# tsop_pcb.net
KiCad netlist of a schematic drawn in EAGLE
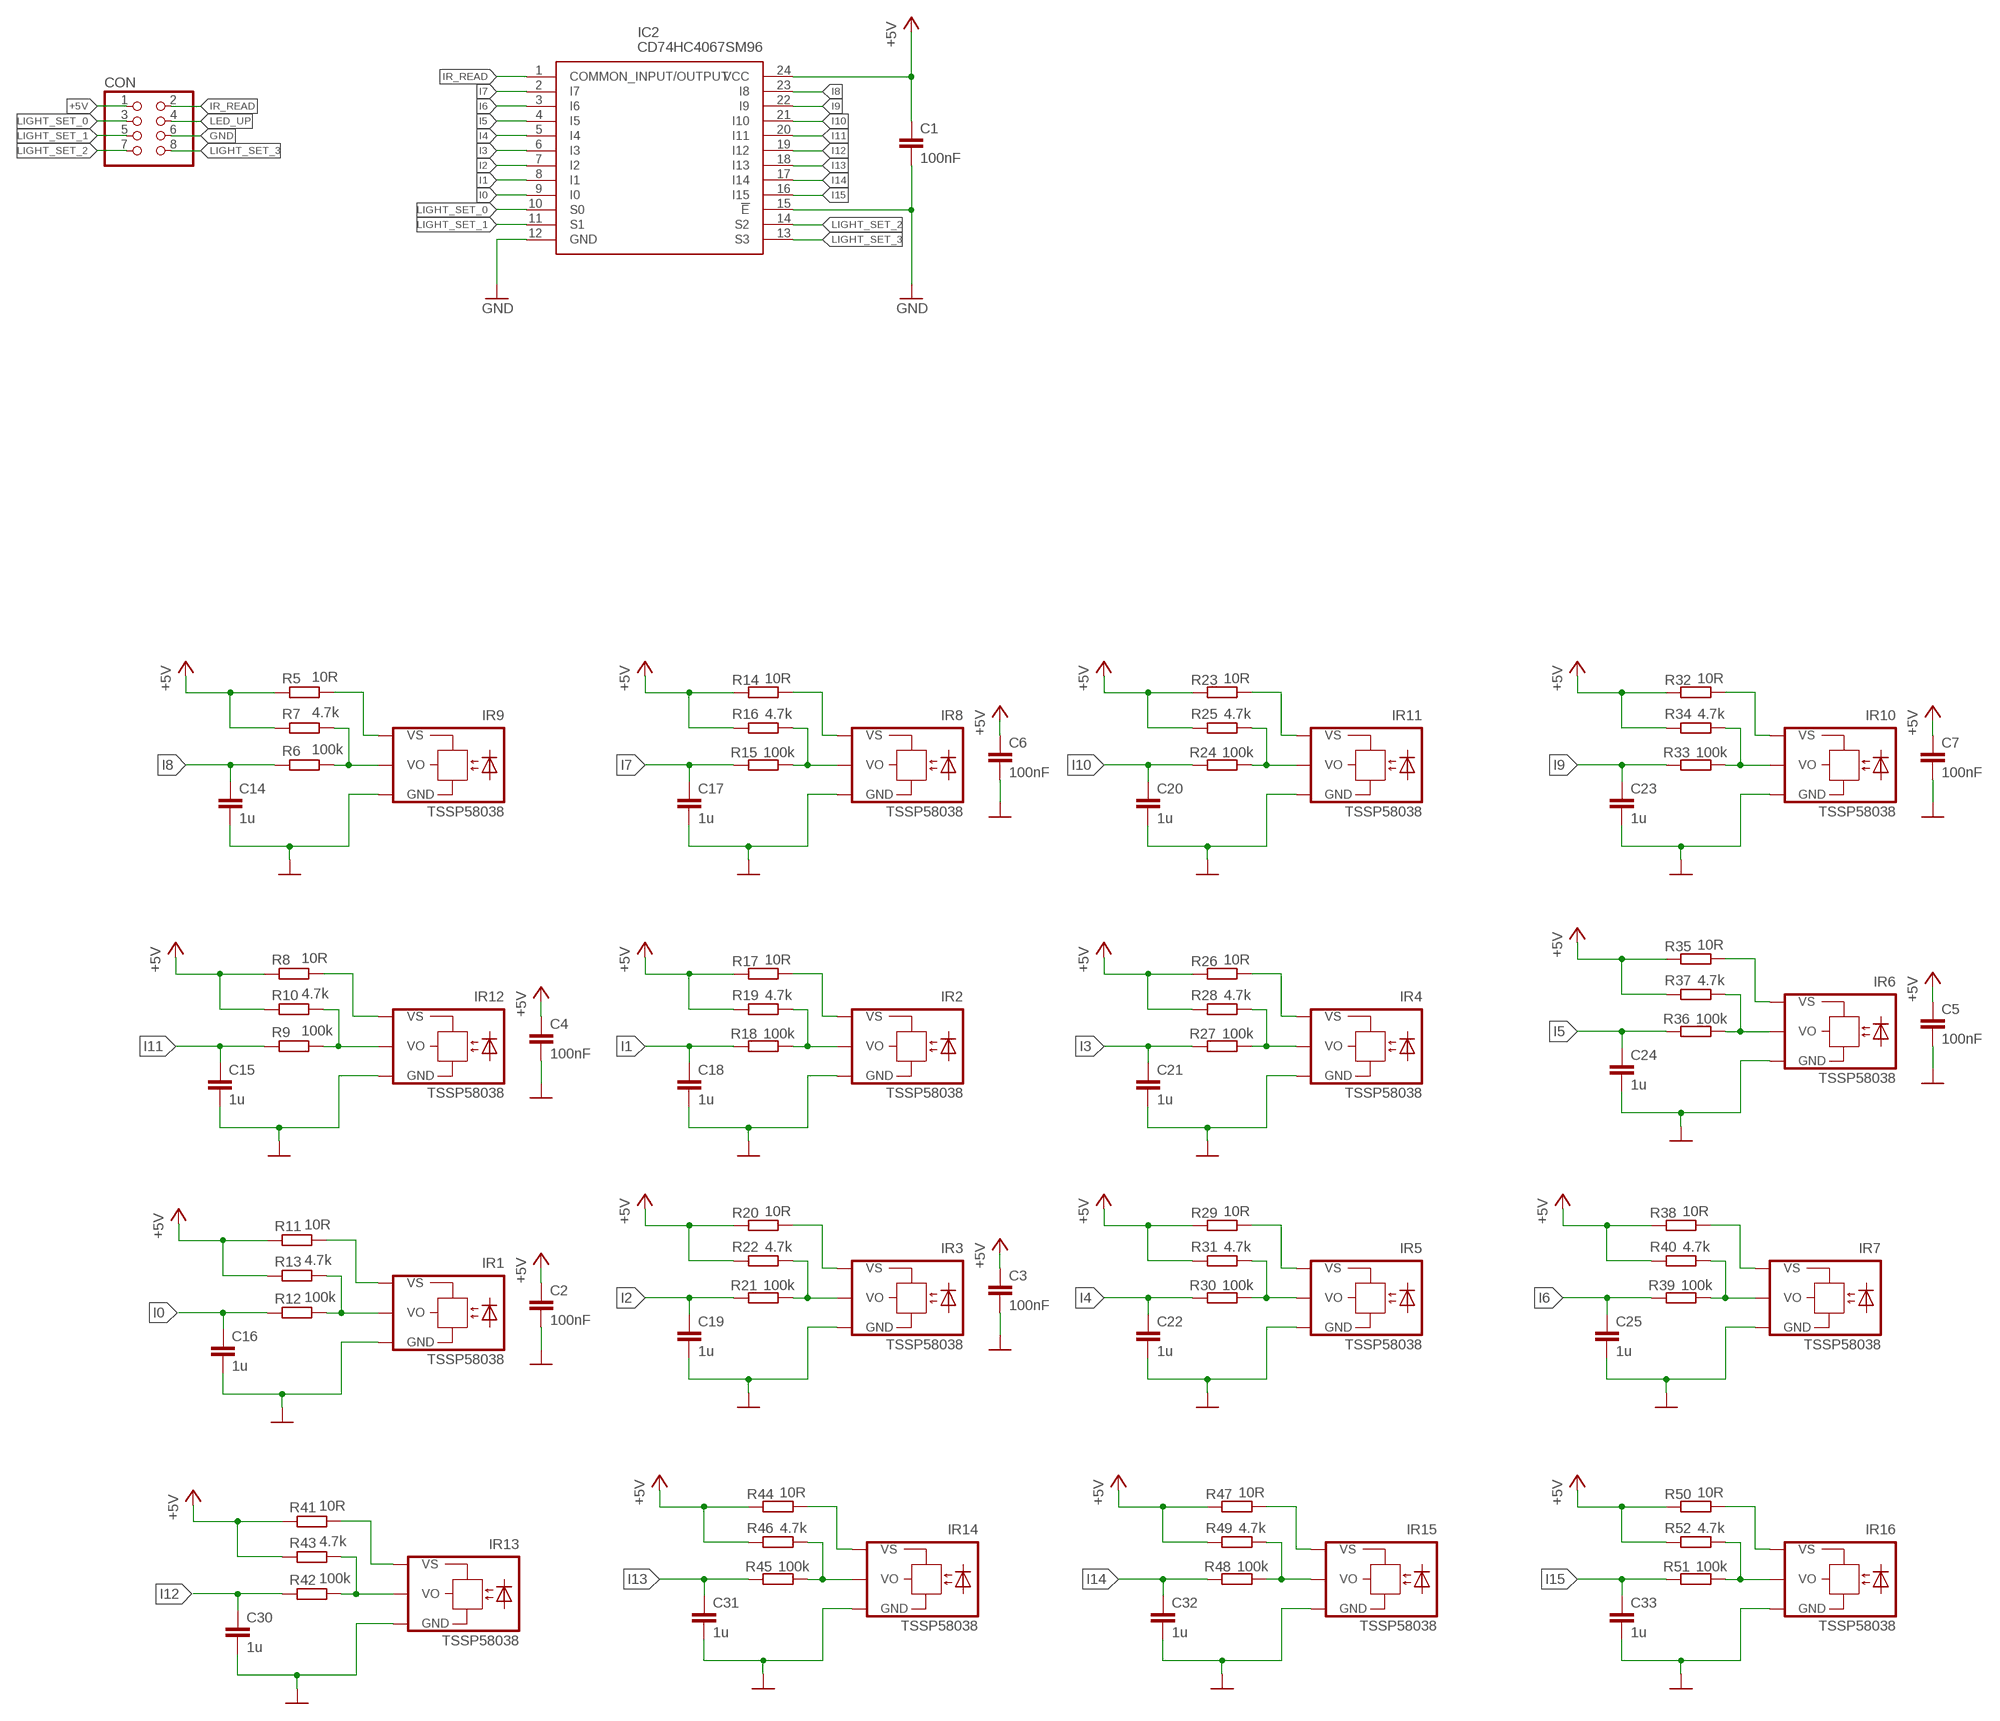
[diagram p0: schematic, sheet 1]

(export (version "E")
  (design (tool "Eeschema 10.0.6"))
  (components
    (comp (ref "C1")
      (value "100nF")
      (footprint "eagle-import:C0805")
      (libsource (lib "eagle-import") (part "C-EUC0805"))
    )
    (comp (ref "C2")
      (value "100nF")
      (footprint "eagle-import:C0805")
      (libsource (lib "eagle-import") (part "C-EUC0805"))
    )
    (comp (ref "C3")
      (value "100nF")
      (footprint "eagle-import:C0805")
      (libsource (lib "eagle-import") (part "C-EUC0805"))
    )
    (comp (ref "C4")
      (value "100nF")
      (footprint "eagle-import:C0805")
      (libsource (lib "eagle-import") (part "C-EUC0805"))
    )
    (comp (ref "C5")
      (value "100nF")
      (footprint "eagle-import:C0805")
      (libsource (lib "eagle-import") (part "C-EUC0805"))
    )
    (comp (ref "C6")
      (value "100nF")
      (footprint "eagle-import:C0805")
      (libsource (lib "eagle-import") (part "C-EUC0805"))
    )
    (comp (ref "C7")
      (value "100nF")
      (footprint "eagle-import:C0805")
      (libsource (lib "eagle-import") (part "C-EUC0805"))
    )
    (comp (ref "C14")
      (value "1u")
      (footprint "eagle-import:C0805")
      (libsource (lib "eagle-import") (part "C-EUC0805"))
    )
    (comp (ref "C15")
      (value "1u")
      (footprint "eagle-import:C0805")
      (libsource (lib "eagle-import") (part "C-EUC0805"))
    )
    (comp (ref "C16")
      (value "1u")
      (footprint "eagle-import:C0805")
      (libsource (lib "eagle-import") (part "C-EUC0805"))
    )
    (comp (ref "C17")
      (value "1u")
      (footprint "eagle-import:C0805")
      (libsource (lib "eagle-import") (part "C-EUC0805"))
    )
    (comp (ref "C18")
      (value "1u")
      (footprint "eagle-import:C0805")
      (libsource (lib "eagle-import") (part "C-EUC0805"))
    )
    (comp (ref "C19")
      (value "1u")
      (footprint "eagle-import:C0805")
      (libsource (lib "eagle-import") (part "C-EUC0805"))
    )
    (comp (ref "C20")
      (value "1u")
      (footprint "eagle-import:C0805")
      (libsource (lib "eagle-import") (part "C-EUC0805"))
    )
    (comp (ref "C21")
      (value "1u")
      (footprint "eagle-import:C0805")
      (libsource (lib "eagle-import") (part "C-EUC0805"))
    )
    (comp (ref "C22")
      (value "1u")
      (footprint "eagle-import:C0805")
      (libsource (lib "eagle-import") (part "C-EUC0805"))
    )
    (comp (ref "C23")
      (value "1u")
      (footprint "eagle-import:C0805")
      (libsource (lib "eagle-import") (part "C-EUC0805"))
    )
    (comp (ref "C24")
      (value "1u")
      (footprint "eagle-import:C0805")
      (libsource (lib "eagle-import") (part "C-EUC0805"))
    )
    (comp (ref "C25")
      (value "1u")
      (footprint "eagle-import:C0805")
      (libsource (lib "eagle-import") (part "C-EUC0805"))
    )
    (comp (ref "C30")
      (value "1u")
      (footprint "eagle-import:C0805")
      (libsource (lib "eagle-import") (part "C-EUC0805"))
    )
    (comp (ref "C31")
      (value "1u")
      (footprint "eagle-import:C0805")
      (libsource (lib "eagle-import") (part "C-EUC0805"))
    )
    (comp (ref "C32")
      (value "1u")
      (footprint "eagle-import:C0805")
      (libsource (lib "eagle-import") (part "C-EUC0805"))
    )
    (comp (ref "C33")
      (value "1u")
      (footprint "eagle-import:C0805")
      (libsource (lib "eagle-import") (part "C-EUC0805"))
    )
    (comp (ref "CON")
      (value "PINHD-2X4")
      (footprint "eagle-import:2X04")
      (libsource (lib "eagle-import") (part "PINHD-2X4"))
    )
    (comp (ref "IC2")
      (value "CD74HC4067SM96")
      (footprint "eagle-import:SOP65P780X200-24N")
      (fields (field (name "MOUSER_PART_NUMBER") "595-CD74HC4067SM96"))
      (libsource (lib "eagle-import") (part "CD74HC4067SM96"))
    )
    (comp (ref "IR1")
      (value "TSSP58038")
      (footprint "eagle-import:TSOP")
      (fields (field (name "MF") "Vishay") (field (name "MP") "TSOP4038"))
      (libsource (lib "eagle-import") (part "TSOP4038"))
    )
    (comp (ref "IR2")
      (value "TSSP58038")
      (footprint "eagle-import:TSOP")
      (fields (field (name "MF") "Vishay") (field (name "MP") "TSOP4038"))
      (libsource (lib "eagle-import") (part "TSOP4038"))
    )
    (comp (ref "IR3")
      (value "TSSP58038")
      (footprint "eagle-import:TSOP")
      (fields (field (name "MF") "Vishay") (field (name "MP") "TSOP4038"))
      (libsource (lib "eagle-import") (part "TSOP4038"))
    )
    (comp (ref "IR4")
      (value "TSSP58038")
      (footprint "eagle-import:TSOP")
      (fields (field (name "MF") "Vishay") (field (name "MP") "TSOP4038"))
      (libsource (lib "eagle-import") (part "TSOP4038"))
    )
    (comp (ref "IR5")
      (value "TSSP58038")
      (footprint "eagle-import:TSOP")
      (fields (field (name "MF") "Vishay") (field (name "MP") "TSOP4038"))
      (libsource (lib "eagle-import") (part "TSOP4038"))
    )
    (comp (ref "IR6")
      (value "TSSP58038")
      (footprint "eagle-import:TSOP")
      (fields (field (name "MF") "Vishay") (field (name "MP") "TSOP4038"))
      (libsource (lib "eagle-import") (part "TSOP4038"))
    )
    (comp (ref "IR7")
      (value "TSSP58038")
      (footprint "eagle-import:TSOP")
      (fields (field (name "MF") "Vishay") (field (name "MP") "TSOP4038"))
      (libsource (lib "eagle-import") (part "TSOP4038"))
    )
    (comp (ref "IR8")
      (value "TSSP58038")
      (footprint "eagle-import:TSOP")
      (fields (field (name "MF") "Vishay") (field (name "MP") "TSOP4038"))
      (libsource (lib "eagle-import") (part "TSOP4038"))
    )
    (comp (ref "IR9")
      (value "TSSP58038")
      (footprint "eagle-import:TSOP")
      (fields (field (name "MF") "Vishay") (field (name "MP") "TSOP4038"))
      (libsource (lib "eagle-import") (part "TSOP4038"))
    )
    (comp (ref "IR10")
      (value "TSSP58038")
      (footprint "eagle-import:TSOP")
      (fields (field (name "MF") "Vishay") (field (name "MP") "TSOP4038"))
      (libsource (lib "eagle-import") (part "TSOP4038"))
    )
    (comp (ref "IR11")
      (value "TSSP58038")
      (footprint "eagle-import:TSOP")
      (fields (field (name "MF") "Vishay") (field (name "MP") "TSOP4038"))
      (libsource (lib "eagle-import") (part "TSOP4038"))
    )
    (comp (ref "IR12")
      (value "TSSP58038")
      (footprint "eagle-import:TSOP")
      (fields (field (name "MF") "Vishay") (field (name "MP") "TSOP4038"))
      (libsource (lib "eagle-import") (part "TSOP4038"))
    )
    (comp (ref "IR13")
      (value "TSSP58038")
      (footprint "eagle-import:TSOP")
      (fields (field (name "MF") "Vishay") (field (name "MP") "TSOP4038"))
      (libsource (lib "eagle-import") (part "TSOP4038"))
    )
    (comp (ref "IR14")
      (value "TSSP58038")
      (footprint "eagle-import:TSOP")
      (fields (field (name "MF") "Vishay") (field (name "MP") "TSOP4038"))
      (libsource (lib "eagle-import") (part "TSOP4038"))
    )
    (comp (ref "IR15")
      (value "TSSP58038")
      (footprint "eagle-import:TSOP")
      (fields (field (name "MF") "Vishay") (field (name "MP") "TSOP4038"))
      (libsource (lib "eagle-import") (part "TSOP4038"))
    )
    (comp (ref "IR16")
      (value "TSSP58038")
      (footprint "eagle-import:TSOP")
      (fields (field (name "MF") "Vishay") (field (name "MP") "TSOP4038"))
      (libsource (lib "eagle-import") (part "TSOP4038"))
    )
    (comp (ref "R5")
      (value "10R")
      (footprint "eagle-import:R0805")
      (libsource (lib "eagle-import") (part "R-EU_R0805"))
    )
    (comp (ref "R6")
      (value "100k")
      (footprint "eagle-import:R0805")
      (libsource (lib "eagle-import") (part "R-EU_R0805"))
    )
    (comp (ref "R7")
      (value "4.7k")
      (footprint "eagle-import:R0805")
      (libsource (lib "eagle-import") (part "R-EU_R0805"))
    )
    (comp (ref "R8")
      (value "10R")
      (footprint "eagle-import:R0805")
      (libsource (lib "eagle-import") (part "R-EU_R0805"))
    )
    (comp (ref "R9")
      (value "100k")
      (footprint "eagle-import:R0805")
      (libsource (lib "eagle-import") (part "R-EU_R0805"))
    )
    (comp (ref "R10")
      (value "4.7k")
      (footprint "eagle-import:R0805")
      (libsource (lib "eagle-import") (part "R-EU_R0805"))
    )
    (comp (ref "R11")
      (value "10R")
      (footprint "eagle-import:R0805")
      (libsource (lib "eagle-import") (part "R-EU_R0805"))
    )
    (comp (ref "R12")
      (value "100k")
      (footprint "eagle-import:R0805")
      (libsource (lib "eagle-import") (part "R-EU_R0805"))
    )
    (comp (ref "R13")
      (value "4.7k")
      (footprint "eagle-import:R0805")
      (libsource (lib "eagle-import") (part "R-EU_R0805"))
    )
    (comp (ref "R14")
      (value "10R")
      (footprint "eagle-import:R0805")
      (libsource (lib "eagle-import") (part "R-EU_R0805"))
    )
    (comp (ref "R15")
      (value "100k")
      (footprint "eagle-import:R0805")
      (libsource (lib "eagle-import") (part "R-EU_R0805"))
    )
    (comp (ref "R16")
      (value "4.7k")
      (footprint "eagle-import:R0805")
      (libsource (lib "eagle-import") (part "R-EU_R0805"))
    )
    (comp (ref "R17")
      (value "10R")
      (footprint "eagle-import:R0805")
      (libsource (lib "eagle-import") (part "R-EU_R0805"))
    )
    (comp (ref "R18")
      (value "100k")
      (footprint "eagle-import:R0805")
      (libsource (lib "eagle-import") (part "R-EU_R0805"))
    )
    (comp (ref "R19")
      (value "4.7k")
      (footprint "eagle-import:R0805")
      (libsource (lib "eagle-import") (part "R-EU_R0805"))
    )
    (comp (ref "R20")
      (value "10R")
      (footprint "eagle-import:R0805")
      (libsource (lib "eagle-import") (part "R-EU_R0805"))
    )
    (comp (ref "R21")
      (value "100k")
      (footprint "eagle-import:R0805")
      (libsource (lib "eagle-import") (part "R-EU_R0805"))
    )
    (comp (ref "R22")
      (value "4.7k")
      (footprint "eagle-import:R0805")
      (libsource (lib "eagle-import") (part "R-EU_R0805"))
    )
    (comp (ref "R23")
      (value "10R")
      (footprint "eagle-import:R0805")
      (libsource (lib "eagle-import") (part "R-EU_R0805"))
    )
    (comp (ref "R24")
      (value "100k")
      (footprint "eagle-import:R0805")
      (libsource (lib "eagle-import") (part "R-EU_R0805"))
    )
    (comp (ref "R25")
      (value "4.7k")
      (footprint "eagle-import:R0805")
      (libsource (lib "eagle-import") (part "R-EU_R0805"))
    )
    (comp (ref "R26")
      (value "10R")
      (footprint "eagle-import:R0805")
      (libsource (lib "eagle-import") (part "R-EU_R0805"))
    )
    (comp (ref "R27")
      (value "100k")
      (footprint "eagle-import:R0805")
      (libsource (lib "eagle-import") (part "R-EU_R0805"))
    )
    (comp (ref "R28")
      (value "4.7k")
      (footprint "eagle-import:R0805")
      (libsource (lib "eagle-import") (part "R-EU_R0805"))
    )
    (comp (ref "R29")
      (value "10R")
      (footprint "eagle-import:R0805")
      (libsource (lib "eagle-import") (part "R-EU_R0805"))
    )
    (comp (ref "R30")
      (value "100k")
      (footprint "eagle-import:R0805")
      (libsource (lib "eagle-import") (part "R-EU_R0805"))
    )
    (comp (ref "R31")
      (value "4.7k")
      (footprint "eagle-import:R0805")
      (libsource (lib "eagle-import") (part "R-EU_R0805"))
    )
    (comp (ref "R32")
      (value "10R")
      (footprint "eagle-import:R0805")
      (libsource (lib "eagle-import") (part "R-EU_R0805"))
    )
    (comp (ref "R33")
      (value "100k")
      (footprint "eagle-import:R0805")
      (libsource (lib "eagle-import") (part "R-EU_R0805"))
    )
    (comp (ref "R34")
      (value "4.7k")
      (footprint "eagle-import:R0805")
      (libsource (lib "eagle-import") (part "R-EU_R0805"))
    )
    (comp (ref "R35")
      (value "10R")
      (footprint "eagle-import:R0805")
      (libsource (lib "eagle-import") (part "R-EU_R0805"))
    )
    (comp (ref "R36")
      (value "100k")
      (footprint "eagle-import:R0805")
      (libsource (lib "eagle-import") (part "R-EU_R0805"))
    )
    (comp (ref "R37")
      (value "4.7k")
      (footprint "eagle-import:R0805")
      (libsource (lib "eagle-import") (part "R-EU_R0805"))
    )
    (comp (ref "R38")
      (value "10R")
      (footprint "eagle-import:R0805")
      (libsource (lib "eagle-import") (part "R-EU_R0805"))
    )
    (comp (ref "R39")
      (value "100k")
      (footprint "eagle-import:R0805")
      (libsource (lib "eagle-import") (part "R-EU_R0805"))
    )
    (comp (ref "R40")
      (value "4.7k")
      (footprint "eagle-import:R0805")
      (libsource (lib "eagle-import") (part "R-EU_R0805"))
    )
    (comp (ref "R41")
      (value "10R")
      (footprint "eagle-import:R0805")
      (libsource (lib "eagle-import") (part "R-EU_R0805"))
    )
    (comp (ref "R42")
      (value "100k")
      (footprint "eagle-import:R0805")
      (libsource (lib "eagle-import") (part "R-EU_R0805"))
    )
    (comp (ref "R43")
      (value "4.7k")
      (footprint "eagle-import:R0805")
      (libsource (lib "eagle-import") (part "R-EU_R0805"))
    )
    (comp (ref "R44")
      (value "10R")
      (footprint "eagle-import:R0805")
      (libsource (lib "eagle-import") (part "R-EU_R0805"))
    )
    (comp (ref "R45")
      (value "100k")
      (footprint "eagle-import:R0805")
      (libsource (lib "eagle-import") (part "R-EU_R0805"))
    )
    (comp (ref "R46")
      (value "4.7k")
      (footprint "eagle-import:R0805")
      (libsource (lib "eagle-import") (part "R-EU_R0805"))
    )
    (comp (ref "R47")
      (value "10R")
      (footprint "eagle-import:R0805")
      (libsource (lib "eagle-import") (part "R-EU_R0805"))
    )
    (comp (ref "R48")
      (value "100k")
      (footprint "eagle-import:R0805")
      (libsource (lib "eagle-import") (part "R-EU_R0805"))
    )
    (comp (ref "R49")
      (value "4.7k")
      (footprint "eagle-import:R0805")
      (libsource (lib "eagle-import") (part "R-EU_R0805"))
    )
    (comp (ref "R50")
      (value "10R")
      (footprint "eagle-import:R0805")
      (libsource (lib "eagle-import") (part "R-EU_R0805"))
    )
    (comp (ref "R51")
      (value "100k")
      (footprint "eagle-import:R0805")
      (libsource (lib "eagle-import") (part "R-EU_R0805"))
    )
    (comp (ref "R52")
      (value "4.7k")
      (footprint "eagle-import:R0805")
      (libsource (lib "eagle-import") (part "R-EU_R0805"))
    )
  )
  (nets
    (net (code "1") (name "+5V") (class "Default")
      (node (ref "C1") (pin "1") (pinfunction "1_1") (pintype "passive"))
      (node (ref "C2") (pin "1") (pinfunction "1_1") (pintype "passive"))
      (node (ref "C3") (pin "1") (pinfunction "1_1") (pintype "passive"))
      (node (ref "C4") (pin "1") (pinfunction "1_1") (pintype "passive"))
      (node (ref "C5") (pin "1") (pinfunction "1_1") (pintype "passive"))
      (node (ref "C6") (pin "1") (pinfunction "1_1") (pintype "passive"))
      (node (ref "C7") (pin "1") (pinfunction "1_1") (pintype "passive"))
      (node (ref "CON") (pin "1") (pinfunction "1_1") (pintype "passive"))
      (node (ref "IC2") (pin "24") (pinfunction "VCC_24") (pintype "bidirectional"))
      (node (ref "R10") (pin "1") (pinfunction "1_1") (pintype "passive"))
      (node (ref "R11") (pin "1") (pinfunction "1_1") (pintype "passive"))
      (node (ref "R13") (pin "1") (pinfunction "1_1") (pintype "passive"))
      (node (ref "R14") (pin "1") (pinfunction "1_1") (pintype "passive"))
      (node (ref "R16") (pin "1") (pinfunction "1_1") (pintype "passive"))
      (node (ref "R17") (pin "1") (pinfunction "1_1") (pintype "passive"))
      (node (ref "R19") (pin "1") (pinfunction "1_1") (pintype "passive"))
      (node (ref "R20") (pin "1") (pinfunction "1_1") (pintype "passive"))
      (node (ref "R22") (pin "1") (pinfunction "1_1") (pintype "passive"))
      (node (ref "R23") (pin "1") (pinfunction "1_1") (pintype "passive"))
      (node (ref "R25") (pin "1") (pinfunction "1_1") (pintype "passive"))
      (node (ref "R26") (pin "1") (pinfunction "1_1") (pintype "passive"))
      (node (ref "R28") (pin "1") (pinfunction "1_1") (pintype "passive"))
      (node (ref "R29") (pin "1") (pinfunction "1_1") (pintype "passive"))
      (node (ref "R31") (pin "1") (pinfunction "1_1") (pintype "passive"))
      (node (ref "R32") (pin "1") (pinfunction "1_1") (pintype "passive"))
      (node (ref "R34") (pin "1") (pinfunction "1_1") (pintype "passive"))
      (node (ref "R35") (pin "1") (pinfunction "1_1") (pintype "passive"))
      (node (ref "R37") (pin "1") (pinfunction "1_1") (pintype "passive"))
      (node (ref "R38") (pin "1") (pinfunction "1_1") (pintype "passive"))
      (node (ref "R40") (pin "1") (pinfunction "1_1") (pintype "passive"))
      (node (ref "R41") (pin "1") (pinfunction "1_1") (pintype "passive"))
      (node (ref "R43") (pin "1") (pinfunction "1_1") (pintype "passive"))
      (node (ref "R44") (pin "1") (pinfunction "1_1") (pintype "passive"))
      (node (ref "R46") (pin "1") (pinfunction "1_1") (pintype "passive"))
      (node (ref "R47") (pin "1") (pinfunction "1_1") (pintype "passive"))
      (node (ref "R49") (pin "1") (pinfunction "1_1") (pintype "passive"))
      (node (ref "R5") (pin "1") (pinfunction "1_1") (pintype "passive"))
      (node (ref "R50") (pin "1") (pinfunction "1_1") (pintype "passive"))
      (node (ref "R52") (pin "1") (pinfunction "1_1") (pintype "passive"))
      (node (ref "R7") (pin "1") (pinfunction "1_1") (pintype "passive"))
      (node (ref "R8") (pin "1") (pinfunction "1_1") (pintype "passive"))
    )
    (net (code "2") (name "GND") (class "Default")
      (node (ref "C1") (pin "2") (pinfunction "2_2") (pintype "passive"))
      (node (ref "C14") (pin "2") (pinfunction "2_2") (pintype "passive"))
      (node (ref "C15") (pin "2") (pinfunction "2_2") (pintype "passive"))
      (node (ref "C16") (pin "2") (pinfunction "2_2") (pintype "passive"))
      (node (ref "C17") (pin "2") (pinfunction "2_2") (pintype "passive"))
      (node (ref "C18") (pin "2") (pinfunction "2_2") (pintype "passive"))
      (node (ref "C19") (pin "2") (pinfunction "2_2") (pintype "passive"))
      (node (ref "C2") (pin "2") (pinfunction "2_2") (pintype "passive"))
      (node (ref "C20") (pin "2") (pinfunction "2_2") (pintype "passive"))
      (node (ref "C21") (pin "2") (pinfunction "2_2") (pintype "passive"))
      (node (ref "C22") (pin "2") (pinfunction "2_2") (pintype "passive"))
      (node (ref "C23") (pin "2") (pinfunction "2_2") (pintype "passive"))
      (node (ref "C24") (pin "2") (pinfunction "2_2") (pintype "passive"))
      (node (ref "C25") (pin "2") (pinfunction "2_2") (pintype "passive"))
      (node (ref "C3") (pin "2") (pinfunction "2_2") (pintype "passive"))
      (node (ref "C30") (pin "2") (pinfunction "2_2") (pintype "passive"))
      (node (ref "C31") (pin "2") (pinfunction "2_2") (pintype "passive"))
      (node (ref "C32") (pin "2") (pinfunction "2_2") (pintype "passive"))
      (node (ref "C33") (pin "2") (pinfunction "2_2") (pintype "passive"))
      (node (ref "C4") (pin "2") (pinfunction "2_2") (pintype "passive"))
      (node (ref "C5") (pin "2") (pinfunction "2_2") (pintype "passive"))
      (node (ref "C6") (pin "2") (pinfunction "2_2") (pintype "passive"))
      (node (ref "C7") (pin "2") (pinfunction "2_2") (pintype "passive"))
      (node (ref "CON") (pin "6") (pinfunction "6_6") (pintype "passive"))
      (node (ref "IC2") (pin "12") (pinfunction "GND_12") (pintype "bidirectional"))
      (node (ref "IC2") (pin "15") (pinfunction "~{E}_15") (pintype "bidirectional"))
      (node (ref "IR1") (pin "GND") (pinfunction "GND_GND") (pintype "power_in"))
      (node (ref "IR10") (pin "GND") (pinfunction "GND_GND") (pintype "power_in"))
      (node (ref "IR11") (pin "GND") (pinfunction "GND_GND") (pintype "power_in"))
      (node (ref "IR12") (pin "GND") (pinfunction "GND_GND") (pintype "power_in"))
      (node (ref "IR13") (pin "GND") (pinfunction "GND_GND") (pintype "power_in"))
      (node (ref "IR14") (pin "GND") (pinfunction "GND_GND") (pintype "power_in"))
      (node (ref "IR15") (pin "GND") (pinfunction "GND_GND") (pintype "power_in"))
      (node (ref "IR16") (pin "GND") (pinfunction "GND_GND") (pintype "power_in"))
      (node (ref "IR2") (pin "GND") (pinfunction "GND_GND") (pintype "power_in"))
      (node (ref "IR3") (pin "GND") (pinfunction "GND_GND") (pintype "power_in"))
      (node (ref "IR4") (pin "GND") (pinfunction "GND_GND") (pintype "power_in"))
      (node (ref "IR5") (pin "GND") (pinfunction "GND_GND") (pintype "power_in"))
      (node (ref "IR6") (pin "GND") (pinfunction "GND_GND") (pintype "power_in"))
      (node (ref "IR7") (pin "GND") (pinfunction "GND_GND") (pintype "power_in"))
      (node (ref "IR8") (pin "GND") (pinfunction "GND_GND") (pintype "power_in"))
      (node (ref "IR9") (pin "GND") (pinfunction "GND_GND") (pintype "power_in"))
    )
    (net (code "3") (name "I0") (class "Default")
      (node (ref "C16") (pin "1") (pinfunction "1_1") (pintype "passive"))
      (node (ref "IC2") (pin "9") (pinfunction "I0_9") (pintype "bidirectional"))
      (node (ref "R12") (pin "1") (pinfunction "1_1") (pintype "passive"))
    )
    (net (code "4") (name "I1") (class "Default")
      (node (ref "C18") (pin "1") (pinfunction "1_1") (pintype "passive"))
      (node (ref "IC2") (pin "8") (pinfunction "I1_8") (pintype "bidirectional"))
      (node (ref "R18") (pin "1") (pinfunction "1_1") (pintype "passive"))
    )
    (net (code "5") (name "I2") (class "Default")
      (node (ref "C19") (pin "1") (pinfunction "1_1") (pintype "passive"))
      (node (ref "IC2") (pin "7") (pinfunction "I2_7") (pintype "bidirectional"))
      (node (ref "R21") (pin "1") (pinfunction "1_1") (pintype "passive"))
    )
    (net (code "6") (name "I3") (class "Default")
      (node (ref "C21") (pin "1") (pinfunction "1_1") (pintype "passive"))
      (node (ref "IC2") (pin "6") (pinfunction "I3_6") (pintype "bidirectional"))
      (node (ref "R27") (pin "1") (pinfunction "1_1") (pintype "passive"))
    )
    (net (code "7") (name "I4") (class "Default")
      (node (ref "C22") (pin "1") (pinfunction "1_1") (pintype "passive"))
      (node (ref "IC2") (pin "5") (pinfunction "I4_5") (pintype "bidirectional"))
      (node (ref "R30") (pin "1") (pinfunction "1_1") (pintype "passive"))
    )
    (net (code "8") (name "I5") (class "Default")
      (node (ref "C24") (pin "1") (pinfunction "1_1") (pintype "passive"))
      (node (ref "IC2") (pin "4") (pinfunction "I5_4") (pintype "bidirectional"))
      (node (ref "R36") (pin "1") (pinfunction "1_1") (pintype "passive"))
    )
    (net (code "9") (name "I6") (class "Default")
      (node (ref "C25") (pin "1") (pinfunction "1_1") (pintype "passive"))
      (node (ref "IC2") (pin "3") (pinfunction "I6_3") (pintype "bidirectional"))
      (node (ref "R39") (pin "1") (pinfunction "1_1") (pintype "passive"))
    )
    (net (code "10") (name "I7") (class "Default")
      (node (ref "C17") (pin "1") (pinfunction "1_1") (pintype "passive"))
      (node (ref "IC2") (pin "2") (pinfunction "I7_2") (pintype "bidirectional"))
      (node (ref "R15") (pin "1") (pinfunction "1_1") (pintype "passive"))
    )
    (net (code "11") (name "I8") (class "Default")
      (node (ref "C14") (pin "1") (pinfunction "1_1") (pintype "passive"))
      (node (ref "IC2") (pin "23") (pinfunction "I8_23") (pintype "bidirectional"))
      (node (ref "R6") (pin "1") (pinfunction "1_1") (pintype "passive"))
    )
    (net (code "12") (name "I9") (class "Default")
      (node (ref "C23") (pin "1") (pinfunction "1_1") (pintype "passive"))
      (node (ref "IC2") (pin "22") (pinfunction "I9_22") (pintype "bidirectional"))
      (node (ref "R33") (pin "1") (pinfunction "1_1") (pintype "passive"))
    )
    (net (code "13") (name "I10") (class "Default")
      (node (ref "C20") (pin "1") (pinfunction "1_1") (pintype "passive"))
      (node (ref "IC2") (pin "21") (pinfunction "I10_21") (pintype "bidirectional"))
      (node (ref "R24") (pin "1") (pinfunction "1_1") (pintype "passive"))
    )
    (net (code "14") (name "I11") (class "Default")
      (node (ref "C15") (pin "1") (pinfunction "1_1") (pintype "passive"))
      (node (ref "IC2") (pin "20") (pinfunction "I11_20") (pintype "bidirectional"))
      (node (ref "R9") (pin "1") (pinfunction "1_1") (pintype "passive"))
    )
    (net (code "15") (name "I12") (class "Default")
      (node (ref "C30") (pin "1") (pinfunction "1_1") (pintype "passive"))
      (node (ref "IC2") (pin "19") (pinfunction "I12_19") (pintype "bidirectional"))
      (node (ref "R42") (pin "1") (pinfunction "1_1") (pintype "passive"))
    )
    (net (code "16") (name "I13") (class "Default")
      (node (ref "C31") (pin "1") (pinfunction "1_1") (pintype "passive"))
      (node (ref "IC2") (pin "18") (pinfunction "I13_18") (pintype "bidirectional"))
      (node (ref "R45") (pin "1") (pinfunction "1_1") (pintype "passive"))
    )
    (net (code "17") (name "I14") (class "Default")
      (node (ref "C32") (pin "1") (pinfunction "1_1") (pintype "passive"))
      (node (ref "IC2") (pin "17") (pinfunction "I14_17") (pintype "bidirectional"))
      (node (ref "R48") (pin "1") (pinfunction "1_1") (pintype "passive"))
    )
    (net (code "18") (name "I15") (class "Default")
      (node (ref "C33") (pin "1") (pinfunction "1_1") (pintype "passive"))
      (node (ref "IC2") (pin "16") (pinfunction "I15_16") (pintype "bidirectional"))
      (node (ref "R51") (pin "1") (pinfunction "1_1") (pintype "passive"))
    )
    (net (code "19") (name "IR_READ") (class "Default")
      (node (ref "CON") (pin "2") (pinfunction "2_2") (pintype "passive"))
      (node (ref "IC2") (pin "1") (pinfunction "COMMON_INPUT/OUTPUT_1") (pintype "bidirectional"))
    )
    (net (code "20") (name "LED_UP") (class "Default")
      (node (ref "CON") (pin "4") (pinfunction "4_4") (pintype "passive"))
    )
    (net (code "21") (name "LIGHT_SET_0") (class "Default")
      (node (ref "CON") (pin "3") (pinfunction "3_3") (pintype "passive"))
      (node (ref "IC2") (pin "10") (pinfunction "S0_10") (pintype "bidirectional"))
    )
    (net (code "22") (name "LIGHT_SET_1") (class "Default")
      (node (ref "CON") (pin "5") (pinfunction "5_5") (pintype "passive"))
      (node (ref "IC2") (pin "11") (pinfunction "S1_11") (pintype "bidirectional"))
    )
    (net (code "23") (name "LIGHT_SET_2") (class "Default")
      (node (ref "CON") (pin "7") (pinfunction "7_7") (pintype "passive"))
      (node (ref "IC2") (pin "14") (pinfunction "S2_14") (pintype "bidirectional"))
    )
    (net (code "24") (name "LIGHT_SET_3") (class "Default")
      (node (ref "CON") (pin "8") (pinfunction "8_8") (pintype "passive"))
      (node (ref "IC2") (pin "13") (pinfunction "S3_13") (pintype "bidirectional"))
    )
    (net (code "25") (name "Net-(IR1-PadVO)") (class "Default")
      (node (ref "IR1") (pin "VO") (pinfunction "VO_VO") (pintype "open_collector"))
      (node (ref "R12") (pin "2") (pinfunction "2_2") (pintype "passive"))
      (node (ref "R13") (pin "2") (pinfunction "2_2") (pintype "passive"))
    )
    (net (code "26") (name "Net-(IR1-PadVS)") (class "Default")
      (node (ref "IR1") (pin "VS") (pinfunction "VS_VS") (pintype "power_in"))
      (node (ref "R11") (pin "2") (pinfunction "2_2") (pintype "passive"))
    )
    (net (code "27") (name "Net-(IR2-PadVO)") (class "Default")
      (node (ref "IR2") (pin "VO") (pinfunction "VO_VO") (pintype "open_collector"))
      (node (ref "R18") (pin "2") (pinfunction "2_2") (pintype "passive"))
      (node (ref "R19") (pin "2") (pinfunction "2_2") (pintype "passive"))
    )
    (net (code "28") (name "Net-(IR2-PadVS)") (class "Default")
      (node (ref "IR2") (pin "VS") (pinfunction "VS_VS") (pintype "power_in"))
      (node (ref "R17") (pin "2") (pinfunction "2_2") (pintype "passive"))
    )
    (net (code "29") (name "Net-(IR3-PadVO)") (class "Default")
      (node (ref "IR3") (pin "VO") (pinfunction "VO_VO") (pintype "open_collector"))
      (node (ref "R21") (pin "2") (pinfunction "2_2") (pintype "passive"))
      (node (ref "R22") (pin "2") (pinfunction "2_2") (pintype "passive"))
    )
    (net (code "30") (name "Net-(IR3-PadVS)") (class "Default")
      (node (ref "IR3") (pin "VS") (pinfunction "VS_VS") (pintype "power_in"))
      (node (ref "R20") (pin "2") (pinfunction "2_2") (pintype "passive"))
    )
    (net (code "31") (name "Net-(IR4-PadVO)") (class "Default")
      (node (ref "IR4") (pin "VO") (pinfunction "VO_VO") (pintype "open_collector"))
      (node (ref "R27") (pin "2") (pinfunction "2_2") (pintype "passive"))
      (node (ref "R28") (pin "2") (pinfunction "2_2") (pintype "passive"))
    )
    (net (code "32") (name "Net-(IR4-PadVS)") (class "Default")
      (node (ref "IR4") (pin "VS") (pinfunction "VS_VS") (pintype "power_in"))
      (node (ref "R26") (pin "2") (pinfunction "2_2") (pintype "passive"))
    )
    (net (code "33") (name "Net-(IR5-PadVO)") (class "Default")
      (node (ref "IR5") (pin "VO") (pinfunction "VO_VO") (pintype "open_collector"))
      (node (ref "R30") (pin "2") (pinfunction "2_2") (pintype "passive"))
      (node (ref "R31") (pin "2") (pinfunction "2_2") (pintype "passive"))
    )
    (net (code "34") (name "Net-(IR5-PadVS)") (class "Default")
      (node (ref "IR5") (pin "VS") (pinfunction "VS_VS") (pintype "power_in"))
      (node (ref "R29") (pin "2") (pinfunction "2_2") (pintype "passive"))
    )
    (net (code "35") (name "Net-(IR6-PadVO)") (class "Default")
      (node (ref "IR6") (pin "VO") (pinfunction "VO_VO") (pintype "open_collector"))
      (node (ref "R36") (pin "2") (pinfunction "2_2") (pintype "passive"))
      (node (ref "R37") (pin "2") (pinfunction "2_2") (pintype "passive"))
    )
    (net (code "36") (name "Net-(IR6-PadVS)") (class "Default")
      (node (ref "IR6") (pin "VS") (pinfunction "VS_VS") (pintype "power_in"))
      (node (ref "R35") (pin "2") (pinfunction "2_2") (pintype "passive"))
    )
    (net (code "37") (name "Net-(IR7-PadVO)") (class "Default")
      (node (ref "IR7") (pin "VO") (pinfunction "VO_VO") (pintype "open_collector"))
      (node (ref "R39") (pin "2") (pinfunction "2_2") (pintype "passive"))
      (node (ref "R40") (pin "2") (pinfunction "2_2") (pintype "passive"))
    )
    (net (code "38") (name "Net-(IR7-PadVS)") (class "Default")
      (node (ref "IR7") (pin "VS") (pinfunction "VS_VS") (pintype "power_in"))
      (node (ref "R38") (pin "2") (pinfunction "2_2") (pintype "passive"))
    )
    (net (code "39") (name "Net-(IR8-PadVO)") (class "Default")
      (node (ref "IR8") (pin "VO") (pinfunction "VO_VO") (pintype "open_collector"))
      (node (ref "R15") (pin "2") (pinfunction "2_2") (pintype "passive"))
      (node (ref "R16") (pin "2") (pinfunction "2_2") (pintype "passive"))
    )
    (net (code "40") (name "Net-(IR8-PadVS)") (class "Default")
      (node (ref "IR8") (pin "VS") (pinfunction "VS_VS") (pintype "power_in"))
      (node (ref "R14") (pin "2") (pinfunction "2_2") (pintype "passive"))
    )
    (net (code "41") (name "Net-(IR9-PadVO)") (class "Default")
      (node (ref "IR9") (pin "VO") (pinfunction "VO_VO") (pintype "open_collector"))
      (node (ref "R6") (pin "2") (pinfunction "2_2") (pintype "passive"))
      (node (ref "R7") (pin "2") (pinfunction "2_2") (pintype "passive"))
    )
    (net (code "42") (name "Net-(IR9-PadVS)") (class "Default")
      (node (ref "IR9") (pin "VS") (pinfunction "VS_VS") (pintype "power_in"))
      (node (ref "R5") (pin "2") (pinfunction "2_2") (pintype "passive"))
    )
    (net (code "43") (name "Net-(IR10-PadVO)") (class "Default")
      (node (ref "IR10") (pin "VO") (pinfunction "VO_VO") (pintype "open_collector"))
      (node (ref "R33") (pin "2") (pinfunction "2_2") (pintype "passive"))
      (node (ref "R34") (pin "2") (pinfunction "2_2") (pintype "passive"))
    )
    (net (code "44") (name "Net-(IR10-PadVS)") (class "Default")
      (node (ref "IR10") (pin "VS") (pinfunction "VS_VS") (pintype "power_in"))
      (node (ref "R32") (pin "2") (pinfunction "2_2") (pintype "passive"))
    )
    (net (code "45") (name "Net-(IR11-PadVO)") (class "Default")
      (node (ref "IR11") (pin "VO") (pinfunction "VO_VO") (pintype "open_collector"))
      (node (ref "R24") (pin "2") (pinfunction "2_2") (pintype "passive"))
      (node (ref "R25") (pin "2") (pinfunction "2_2") (pintype "passive"))
    )
    (net (code "46") (name "Net-(IR11-PadVS)") (class "Default")
      (node (ref "IR11") (pin "VS") (pinfunction "VS_VS") (pintype "power_in"))
      (node (ref "R23") (pin "2") (pinfunction "2_2") (pintype "passive"))
    )
    (net (code "47") (name "Net-(IR12-PadVO)") (class "Default")
      (node (ref "IR12") (pin "VO") (pinfunction "VO_VO") (pintype "open_collector"))
      (node (ref "R10") (pin "2") (pinfunction "2_2") (pintype "passive"))
      (node (ref "R9") (pin "2") (pinfunction "2_2") (pintype "passive"))
    )
    (net (code "48") (name "Net-(IR12-PadVS)") (class "Default")
      (node (ref "IR12") (pin "VS") (pinfunction "VS_VS") (pintype "power_in"))
      (node (ref "R8") (pin "2") (pinfunction "2_2") (pintype "passive"))
    )
    (net (code "49") (name "Net-(IR13-PadVO)") (class "Default")
      (node (ref "IR13") (pin "VO") (pinfunction "VO_VO") (pintype "open_collector"))
      (node (ref "R42") (pin "2") (pinfunction "2_2") (pintype "passive"))
      (node (ref "R43") (pin "2") (pinfunction "2_2") (pintype "passive"))
    )
    (net (code "50") (name "Net-(IR13-PadVS)") (class "Default")
      (node (ref "IR13") (pin "VS") (pinfunction "VS_VS") (pintype "power_in"))
      (node (ref "R41") (pin "2") (pinfunction "2_2") (pintype "passive"))
    )
    (net (code "51") (name "Net-(IR14-PadVO)") (class "Default")
      (node (ref "IR14") (pin "VO") (pinfunction "VO_VO") (pintype "open_collector"))
      (node (ref "R45") (pin "2") (pinfunction "2_2") (pintype "passive"))
      (node (ref "R46") (pin "2") (pinfunction "2_2") (pintype "passive"))
    )
    (net (code "52") (name "Net-(IR14-PadVS)") (class "Default")
      (node (ref "IR14") (pin "VS") (pinfunction "VS_VS") (pintype "power_in"))
      (node (ref "R44") (pin "2") (pinfunction "2_2") (pintype "passive"))
    )
    (net (code "53") (name "Net-(IR15-PadVO)") (class "Default")
      (node (ref "IR15") (pin "VO") (pinfunction "VO_VO") (pintype "open_collector"))
      (node (ref "R48") (pin "2") (pinfunction "2_2") (pintype "passive"))
      (node (ref "R49") (pin "2") (pinfunction "2_2") (pintype "passive"))
    )
    (net (code "54") (name "Net-(IR15-PadVS)") (class "Default")
      (node (ref "IR15") (pin "VS") (pinfunction "VS_VS") (pintype "power_in"))
      (node (ref "R47") (pin "2") (pinfunction "2_2") (pintype "passive"))
    )
    (net (code "55") (name "Net-(IR16-PadVO)") (class "Default")
      (node (ref "IR16") (pin "VO") (pinfunction "VO_VO") (pintype "open_collector"))
      (node (ref "R51") (pin "2") (pinfunction "2_2") (pintype "passive"))
      (node (ref "R52") (pin "2") (pinfunction "2_2") (pintype "passive"))
    )
    (net (code "56") (name "Net-(IR16-PadVS)") (class "Default")
      (node (ref "IR16") (pin "VS") (pinfunction "VS_VS") (pintype "power_in"))
      (node (ref "R50") (pin "2") (pinfunction "2_2") (pintype "passive"))
    )
  )
)
